# tagon.net
KiCad netlist of a schematic drawn in EAGLE
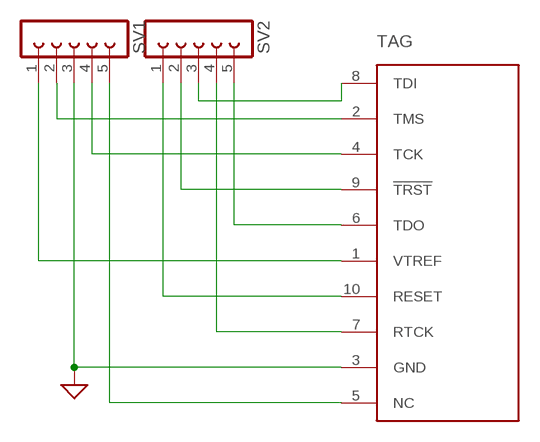
[diagram p0: schematic, sheet 1]

(export (version "E")
  (design (tool "Eeschema 10.0.6"))
  (components
    (comp (ref "SV1")
      (value "FE05-1")
      (footprint "eagle-import:FE05-1")
      (libsource (lib "eagle-import") (part "FE05-1"))
    )
    (comp (ref "SV2")
      (value "FE05-1")
      (footprint "eagle-import:FE05-1")
      (libsource (lib "eagle-import") (part "FE05-1"))
    )
    (comp (ref "TAG")
      (value "TC2050-MCP-NL")
      (footprint "eagle-import:TC2030-MCP-NL")
      (libsource (lib "eagle-import") (part "TC2050-MCP-NL"))
    )
  )
  (nets
    (net (code "1") (name "Net-(TAG-NC)") (class "Default")
      (node (ref "SV1") (pin "5") (pinfunction "5_5") (pintype "passive"))
      (node (ref "TAG") (pin "5") (pinfunction "NC_5") (pintype "bidirectional"))
    )
    (net (code "2") (name "Net-(TAG-RESET)") (class "Default")
      (node (ref "SV2") (pin "1") (pinfunction "1_1") (pintype "passive"))
      (node (ref "TAG") (pin "10") (pinfunction "RESET_10") (pintype "bidirectional"))
    )
    (net (code "3") (name "Net-(TAG-RTCK)") (class "Default")
      (node (ref "SV2") (pin "4") (pinfunction "4_4") (pintype "passive"))
      (node (ref "TAG") (pin "7") (pinfunction "RTCK_7") (pintype "bidirectional"))
    )
    (net (code "4") (name "Net-(TAG-TCK)") (class "Default")
      (node (ref "SV1") (pin "4") (pinfunction "4_4") (pintype "passive"))
      (node (ref "TAG") (pin "4") (pinfunction "TCK_4") (pintype "bidirectional"))
    )
    (net (code "5") (name "Net-(TAG-TDI)") (class "Default")
      (node (ref "SV2") (pin "3") (pinfunction "3_3") (pintype "passive"))
      (node (ref "TAG") (pin "8") (pinfunction "TDI_8") (pintype "bidirectional"))
    )
    (net (code "6") (name "Net-(TAG-TDO)") (class "Default")
      (node (ref "SV2") (pin "5") (pinfunction "5_5") (pintype "passive"))
      (node (ref "TAG") (pin "6") (pinfunction "TDO_6") (pintype "bidirectional"))
    )
    (net (code "7") (name "Net-(TAG-TMS)") (class "Default")
      (node (ref "SV1") (pin "2") (pinfunction "2_2") (pintype "passive"))
      (node (ref "TAG") (pin "2") (pinfunction "TMS_2") (pintype "bidirectional"))
    )
    (net (code "8") (name "Net-(TAG-VTREF)") (class "Default")
      (node (ref "SV1") (pin "1") (pinfunction "1_1") (pintype "passive"))
      (node (ref "TAG") (pin "1") (pinfunction "VTREF_1") (pintype "bidirectional"))
    )
    (net (code "9") (name "Net-(TAG-~{TRST})") (class "Default")
      (node (ref "SV2") (pin "2") (pinfunction "2_2") (pintype "passive"))
      (node (ref "TAG") (pin "9") (pinfunction "~{TRST}_9") (pintype "bidirectional"))
    )
    (net (code "10") (name "SUP") (class "Default")
      (node (ref "SV1") (pin "3") (pinfunction "3_3") (pintype "passive"))
      (node (ref "TAG") (pin "3") (pinfunction "GND_3") (pintype "bidirectional"))
    )
  )
)
